# Headend.net
KiCad netlist of a schematic drawn in EAGLE
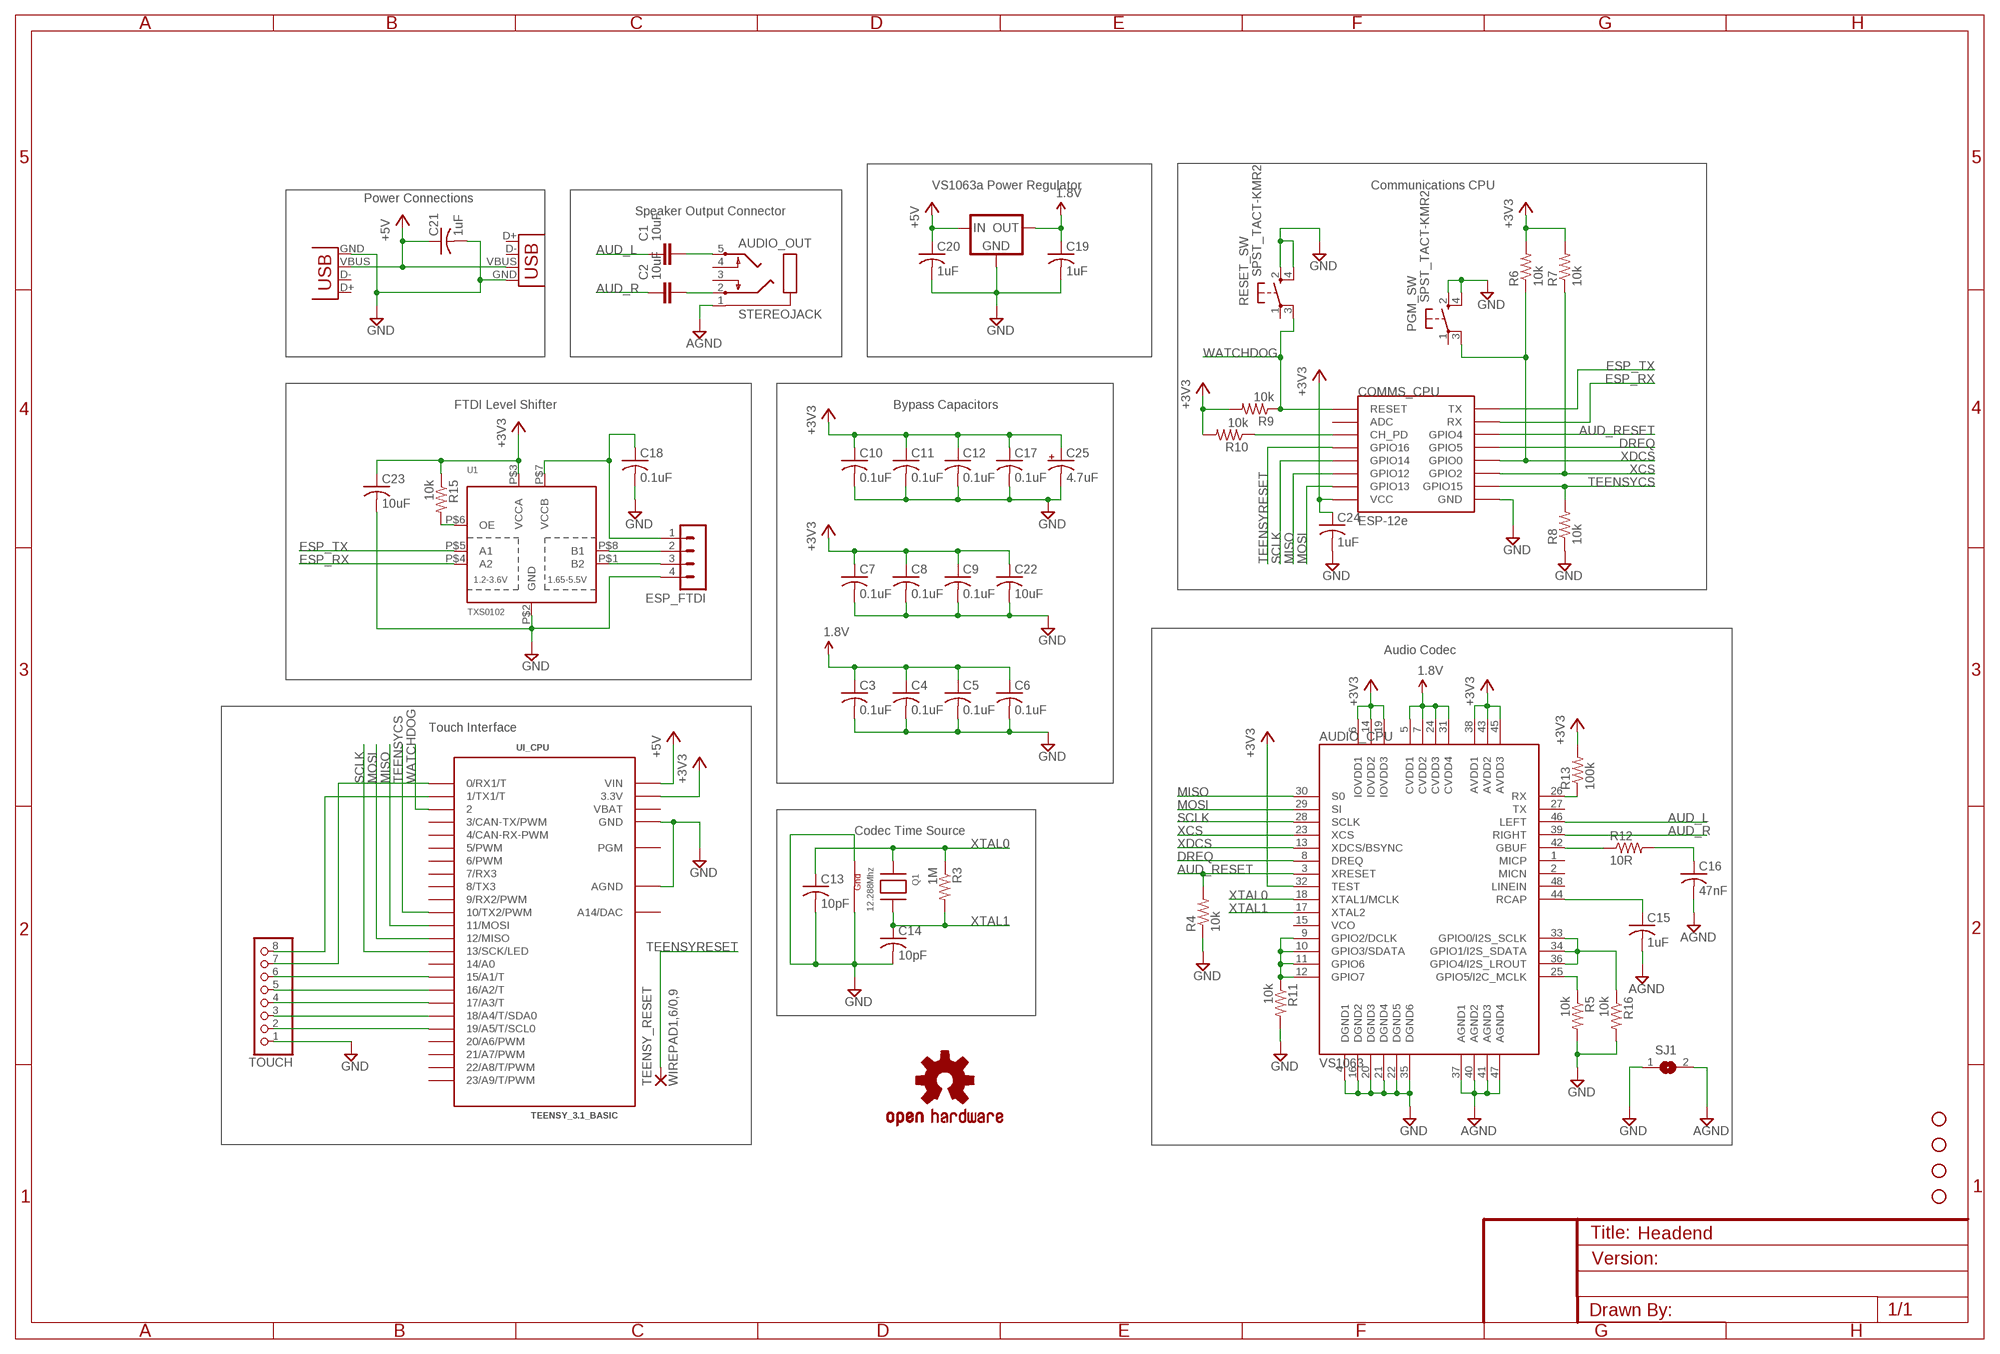
[diagram p0: schematic, sheet 1]

(export (version "E")
  (design (tool "Eeschema 10.0.6"))
  (components
    (comp (ref "AUDIO_CPU")
      (value "VS1063")
      (footprint "eagle-import:LQFP-48")
      (libsource (lib "eagle-import") (part "VS1033"))
    )
    (comp (ref "AUDIO_OUT")
      (value "STEREOJACK")
      (footprint "eagle-import:STX3100")
      (libsource (lib "eagle-import") (part "STEREOJACK"))
    )
    (comp (ref "C1")
      (value "10uF")
      (footprint "eagle-import:C805")
      (libsource (lib "eagle-import") (part "CAPACITOR_NPOL-0805"))
    )
    (comp (ref "C2")
      (value "10uF")
      (footprint "eagle-import:C805")
      (libsource (lib "eagle-import") (part "CAPACITOR_NPOL-0805"))
    )
    (comp (ref "C3")
      (value "0.1uF")
      (footprint "eagle-import:C0402")
      (libsource (lib "eagle-import") (part "C-USC0402"))
    )
    (comp (ref "C4")
      (value "0.1uF")
      (footprint "eagle-import:C0402")
      (libsource (lib "eagle-import") (part "C-USC0402"))
    )
    (comp (ref "C5")
      (value "0.1uF")
      (footprint "eagle-import:C0402")
      (libsource (lib "eagle-import") (part "C-USC0402"))
    )
    (comp (ref "C6")
      (value "0.1uF")
      (footprint "eagle-import:C0402")
      (libsource (lib "eagle-import") (part "C-USC0402"))
    )
    (comp (ref "C7")
      (value "0.1uF")
      (footprint "eagle-import:C0402")
      (libsource (lib "eagle-import") (part "C-USC0402"))
    )
    (comp (ref "C8")
      (value "0.1uF")
      (footprint "eagle-import:C0402")
      (libsource (lib "eagle-import") (part "C-USC0402"))
    )
    (comp (ref "C9")
      (value "0.1uF")
      (footprint "eagle-import:C0402")
      (libsource (lib "eagle-import") (part "C-USC0402"))
    )
    (comp (ref "C10")
      (value "0.1uF")
      (footprint "eagle-import:C0402")
      (libsource (lib "eagle-import") (part "C-USC0402"))
    )
    (comp (ref "C11")
      (value "0.1uF")
      (footprint "eagle-import:C0402")
      (libsource (lib "eagle-import") (part "C-USC0402"))
    )
    (comp (ref "C12")
      (value "0.1uF")
      (footprint "eagle-import:C0402")
      (libsource (lib "eagle-import") (part "C-USC0402"))
    )
    (comp (ref "C13")
      (value "10pF")
      (footprint "eagle-import:C0402")
      (libsource (lib "eagle-import") (part "C-USC0402"))
    )
    (comp (ref "C14")
      (value "10pF")
      (footprint "eagle-import:C0402")
      (libsource (lib "eagle-import") (part "C-USC0402"))
    )
    (comp (ref "C15")
      (value "1uF")
      (footprint "eagle-import:C0402")
      (libsource (lib "eagle-import") (part "C-USC0402"))
    )
    (comp (ref "C16")
      (value "47nF")
      (footprint "eagle-import:C0402")
      (libsource (lib "eagle-import") (part "C-USC0402"))
    )
    (comp (ref "C17")
      (value "0.1uF")
      (footprint "eagle-import:C0402")
      (libsource (lib "eagle-import") (part "C-USC0402"))
    )
    (comp (ref "C18")
      (value "0.1uF")
      (footprint "eagle-import:C0402")
      (libsource (lib "eagle-import") (part "C-USC0402"))
    )
    (comp (ref "C19")
      (value "1uF")
      (footprint "eagle-import:C0603")
      (libsource (lib "eagle-import") (part "C-USC0603"))
    )
    (comp (ref "C20")
      (value "1uF")
      (footprint "eagle-import:C0603")
      (libsource (lib "eagle-import") (part "C-USC0603"))
    )
    (comp (ref "C21")
      (value "1uF")
      (footprint "eagle-import:C0603")
      (libsource (lib "eagle-import") (part "C-USC0603"))
    )
    (comp (ref "C22")
      (value "10uF")
      (footprint "eagle-import:C0402")
      (libsource (lib "eagle-import") (part "C-USC0402"))
    )
    (comp (ref "C23")
      (value "10uF")
      (footprint "eagle-import:C0402")
      (libsource (lib "eagle-import") (part "C-USC0402"))
    )
    (comp (ref "C24")
      (value "1uF")
      (footprint "eagle-import:C0402")
      (libsource (lib "eagle-import") (part "C-USC0402"))
    )
    (comp (ref "C25")
      (value "4.7uF")
      (footprint "eagle-import:PANASONIC_A")
      (libsource (lib "eagle-import") (part "CPOL-USA"))
    )
    (comp (ref "COMMS_CPU")
      (value "ESP-12e")
      (footprint "eagle-import:ESP12-SMD")
      (libsource (lib "eagle-import") (part "ESP12SMD"))
    )
    (comp (ref "ESP_FTDI")
      (value "MA04-1")
      (footprint "eagle-import:MA04-1")
      (libsource (lib "eagle-import") (part "MA04-1"))
    )
    (comp (ref "LOGO1")
      (value "OSHW-LOGOL")
      (footprint "eagle-import:OSHW-LOGO-L")
      (libsource (lib "eagle-import") (part "OSHW-LOGOL"))
    )
    (comp (ref "PGM_SW")
      (value "SPST_TACT-KMR2")
      (footprint "eagle-import:KMR2")
      (libsource (lib "eagle-import") (part "SPST_TACT-KMR2"))
    )
    (comp (ref "POWER_IN")
      (value "USBSMD")
      (footprint "eagle-import:USB-MINIB")
      (libsource (lib "eagle-import") (part "USBSMD"))
    )
    (comp (ref "Q1")
      (value "12.288Mhz")
      (footprint "eagle-import:NX3225")
      (libsource (lib "eagle-import") (part "XTAL-4-3225"))
    )
    (comp (ref "R3")
      (value "1M")
      (footprint "eagle-import:R0402")
      (libsource (lib "eagle-import") (part "R-US_R0402"))
    )
    (comp (ref "R4")
      (value "10k")
      (footprint "eagle-import:R0402")
      (libsource (lib "eagle-import") (part "R-US_R0402"))
    )
    (comp (ref "R5")
      (value "10k")
      (footprint "eagle-import:R0402")
      (libsource (lib "eagle-import") (part "R-US_R0402"))
    )
    (comp (ref "R6")
      (value "10k")
      (footprint "eagle-import:R0402")
      (libsource (lib "eagle-import") (part "R-US_R0402"))
    )
    (comp (ref "R7")
      (value "10k")
      (footprint "eagle-import:R0402")
      (libsource (lib "eagle-import") (part "R-US_R0402"))
    )
    (comp (ref "R8")
      (value "10k")
      (footprint "eagle-import:R0402")
      (libsource (lib "eagle-import") (part "R-US_R0402"))
    )
    (comp (ref "R9")
      (value "10k")
      (footprint "eagle-import:R0603")
      (libsource (lib "eagle-import") (part "R-US_R0603"))
    )
    (comp (ref "R10")
      (value "10k")
      (footprint "eagle-import:R0402")
      (libsource (lib "eagle-import") (part "R-US_R0402"))
    )
    (comp (ref "R11")
      (value "10k")
      (footprint "eagle-import:R0402")
      (libsource (lib "eagle-import") (part "R-US_R0402"))
    )
    (comp (ref "R12")
      (value "10R")
      (footprint "eagle-import:R0402")
      (libsource (lib "eagle-import") (part "R-US_R0402"))
    )
    (comp (ref "R13")
      (value "100k")
      (footprint "eagle-import:R0402")
      (libsource (lib "eagle-import") (part "R-US_R0402"))
    )
    (comp (ref "R15")
      (value "10k")
      (footprint "eagle-import:R0402")
      (libsource (lib "eagle-import") (part "R-US_R0402"))
    )
    (comp (ref "R16")
      (value "10k")
      (footprint "eagle-import:R0402")
      (libsource (lib "eagle-import") (part "R-US_R0402"))
    )
    (comp (ref "RESET_SW")
      (value "SPST_TACT-KMR2")
      (footprint "eagle-import:KMR2")
      (libsource (lib "eagle-import") (part "SPST_TACT-KMR2"))
    )
    (comp (ref "SJ1") (value "SJ") (footprint "eagle-import:SJ") (libsource (lib "eagle-import") (part "SJ")))
    (comp (ref "SPEAKER_PWR2")
      (value "USB-A-S")
      (footprint "eagle-import:USB-A-S")
      (libsource (lib "eagle-import") (part "USB-A-S"))
    )
    (comp (ref "STANDOFF1")
      (value "STAND-OFF")
      (footprint "eagle-import:STAND-OFF")
      (libsource (lib "eagle-import") (part "STAND-OFF"))
    )
    (comp (ref "STANDOFF2")
      (value "STAND-OFF")
      (footprint "eagle-import:STAND-OFF")
      (libsource (lib "eagle-import") (part "STAND-OFF"))
    )
    (comp (ref "STANDOFF3")
      (value "STAND-OFF")
      (footprint "eagle-import:STAND-OFF")
      (libsource (lib "eagle-import") (part "STAND-OFF"))
    )
    (comp (ref "STANDOFF4")
      (value "STAND-OFF")
      (footprint "eagle-import:STAND-OFF")
      (libsource (lib "eagle-import") (part "STAND-OFF"))
    )
    (comp (ref "TEENSY_RESET")
      (value "WIREPAD1,6/0,9")
      (footprint "eagle-import:1,6_0,9")
      (libsource (lib "eagle-import") (part "WIREPAD1,6/0,9"))
    )
    (comp (ref "TOUCH")
      (value "PINHD-1X8BIG")
      (footprint "eagle-import:1X08-BIG")
      (libsource (lib "eagle-import") (part "PINHD-1X8BIG"))
    )
    (comp (ref "U1")
      (value "TXS0102")
      (footprint "eagle-import:VFSOP-8")
      (libsource (lib "eagle-import") (part "TXS0102"))
    )
    (comp (ref "U2")
      (value "AP7313")
      (footprint "eagle-import:SOT23")
      (libsource (lib "eagle-import") (part "AP7313"))
    )
    (comp (ref "UI_CPU")
      (value "TEENSY_3.1_BASIC")
      (footprint "eagle-import:TEENSY_3.1_BASIC")
      (libsource (lib "eagle-import") (part "TEENSY_3.1_BASIC"))
    )
  )
  (nets
    (net (code "1") (name "+3V3") (class "Default")
      (node (ref "AUDIO_CPU") (pin "14") (pinfunction "IOVDD2_14") (pintype "bidirectional"))
      (node (ref "AUDIO_CPU") (pin "19") (pinfunction "IOVDD3_19") (pintype "bidirectional"))
      (node (ref "AUDIO_CPU") (pin "32") (pinfunction "TEST_32") (pintype "bidirectional"))
      (node (ref "AUDIO_CPU") (pin "38") (pinfunction "AVDD1_38") (pintype "bidirectional"))
      (node (ref "AUDIO_CPU") (pin "43") (pinfunction "AVDD2_43") (pintype "bidirectional"))
      (node (ref "AUDIO_CPU") (pin "45") (pinfunction "AVDD3_45") (pintype "bidirectional"))
      (node (ref "AUDIO_CPU") (pin "6") (pinfunction "IOVDD1_6") (pintype "bidirectional"))
      (node (ref "C10") (pin "1") (pinfunction "1_1") (pintype "passive"))
      (node (ref "C11") (pin "1") (pinfunction "1_1") (pintype "passive"))
      (node (ref "C12") (pin "1") (pinfunction "1_1") (pintype "passive"))
      (node (ref "C17") (pin "1") (pinfunction "1_1") (pintype "passive"))
      (node (ref "C22") (pin "1") (pinfunction "1_1") (pintype "passive"))
      (node (ref "C23") (pin "1") (pinfunction "1_1") (pintype "passive"))
      (node (ref "C24") (pin "1") (pinfunction "1_1") (pintype "passive"))
      (node (ref "C25") (pin "+") (pinfunction "+_+") (pintype "passive"))
      (node (ref "C7") (pin "1") (pinfunction "1_1") (pintype "passive"))
      (node (ref "C8") (pin "1") (pinfunction "1_1") (pintype "passive"))
      (node (ref "C9") (pin "1") (pinfunction "1_1") (pintype "passive"))
      (node (ref "COMMS_CPU") (pin "VCC") (pinfunction "VCC_VCC") (pintype "bidirectional"))
      (node (ref "R10") (pin "2") (pinfunction "2_2") (pintype "passive"))
      (node (ref "R13") (pin "2") (pinfunction "2_2") (pintype "passive"))
      (node (ref "R15") (pin "1") (pinfunction "1_1") (pintype "passive"))
      (node (ref "R6") (pin "2") (pinfunction "2_2") (pintype "passive"))
      (node (ref "R7") (pin "2") (pinfunction "2_2") (pintype "passive"))
      (node (ref "R9") (pin "2") (pinfunction "2_2") (pintype "passive"))
      (node (ref "U1") (pin "P$3") (pinfunction "VCCA_P$3") (pintype "bidirectional"))
      (node (ref "UI_CPU") (pin "3.3V") (pinfunction "3.3V_3.3V") (pintype "power_in"))
      (node (ref "UI_CPU") (pin "3.3V1") (pinfunction "3.3V_3.3V1") (pintype "power_in"))
    )
    (net (code "2") (name "+5V") (class "Default")
      (node (ref "C20") (pin "1") (pinfunction "1_1") (pintype "passive"))
      (node (ref "C21") (pin "1") (pinfunction "1_1") (pintype "passive"))
      (node (ref "POWER_IN") (pin "VBUS") (pinfunction "VBUS_VBUS") (pintype "bidirectional"))
      (node (ref "SPEAKER_PWR2") (pin "VBUS") (pinfunction "VBUS_VBUS") (pintype "bidirectional"))
      (node (ref "U2") (pin "1") (pinfunction "IN_1") (pintype "input"))
      (node (ref "UI_CPU") (pin "VIN") (pinfunction "VIN_VIN") (pintype "power_in"))
    )
    (net (code "3") (name "/AUD_L") (class "Default")
      (node (ref "AUDIO_CPU") (pin "46") (pinfunction "LEFT_46") (pintype "bidirectional"))
      (node (ref "C1") (pin "1") (pinfunction "1_1") (pintype "passive"))
    )
    (net (code "4") (name "/AUD_R") (class "Default")
      (node (ref "AUDIO_CPU") (pin "39") (pinfunction "RIGHT_39") (pintype "bidirectional"))
      (node (ref "C2") (pin "1") (pinfunction "1_1") (pintype "passive"))
    )
    (net (code "5") (name "/AUD_RESET") (class "Default")
      (node (ref "AUDIO_CPU") (pin "3") (pinfunction "XRESET_3") (pintype "bidirectional"))
      (node (ref "COMMS_CPU") (pin "GPIO4") (pinfunction "GPIO4_GPIO4") (pintype "bidirectional"))
      (node (ref "R4") (pin "2") (pinfunction "2_2") (pintype "passive"))
    )
    (net (code "6") (name "/DREQ") (class "Default")
      (node (ref "AUDIO_CPU") (pin "8") (pinfunction "DREQ_8") (pintype "bidirectional"))
      (node (ref "COMMS_CPU") (pin "GPIO5") (pinfunction "GPIO5_GPIO5") (pintype "bidirectional"))
    )
    (net (code "7") (name "/ESP_RX") (class "Default")
      (node (ref "COMMS_CPU") (pin "RXD0") (pinfunction "RX_RXD0") (pintype "bidirectional"))
      (node (ref "U1") (pin "P$4") (pinfunction "A2_P$4") (pintype "bidirectional"))
    )
    (net (code "8") (name "/ESP_TX") (class "Default")
      (node (ref "COMMS_CPU") (pin "TXD0") (pinfunction "TX_TXD0") (pintype "bidirectional"))
      (node (ref "U1") (pin "P$5") (pinfunction "A1_P$5") (pintype "bidirectional"))
    )
    (net (code "9") (name "/MISO") (class "Default")
      (node (ref "AUDIO_CPU") (pin "30") (pinfunction "S0_30") (pintype "bidirectional"))
      (node (ref "COMMS_CPU") (pin "GPIO12") (pinfunction "GPIO12_GPIO12") (pintype "bidirectional"))
      (node (ref "UI_CPU") (pin "11") (pinfunction "11/MOSI_11") (pintype "bidirectional"))
    )
    (net (code "10") (name "/MOSI") (class "Default")
      (node (ref "AUDIO_CPU") (pin "29") (pinfunction "SI_29") (pintype "bidirectional"))
      (node (ref "COMMS_CPU") (pin "GPIO13") (pinfunction "GPIO13_GPIO13") (pintype "bidirectional"))
      (node (ref "UI_CPU") (pin "12") (pinfunction "12/MISO_12") (pintype "bidirectional"))
    )
    (net (code "11") (name "/SCLK") (class "Default")
      (node (ref "AUDIO_CPU") (pin "28") (pinfunction "SCLK_28") (pintype "bidirectional"))
      (node (ref "COMMS_CPU") (pin "GPIO14") (pinfunction "GPIO14_GPIO14") (pintype "bidirectional"))
      (node (ref "UI_CPU") (pin "13") (pinfunction "13/SCK/LED_13") (pintype "bidirectional"))
    )
    (net (code "12") (name "/TEENSYCS") (class "Default")
      (node (ref "COMMS_CPU") (pin "GPIO15") (pinfunction "GPIO15_GPIO15") (pintype "bidirectional"))
      (node (ref "R8") (pin "2") (pinfunction "2_2") (pintype "passive"))
      (node (ref "UI_CPU") (pin "10") (pinfunction "10/TX2/PWM_10") (pintype "bidirectional"))
    )
    (net (code "13") (name "/TEENSYRESET") (class "Default")
      (node (ref "COMMS_CPU") (pin "GPIO16") (pinfunction "GPIO16_GPIO16") (pintype "bidirectional"))
      (node (ref "TEENSY_RESET") (pin "1") (pinfunction "P_1") (pintype "passive"))
    )
    (net (code "14") (name "/VBAT") (class "Default")
      (node (ref "UI_CPU") (pin "VBAT") (pinfunction "VBAT_VBAT") (pintype "power_in"))
    )
    (net (code "15") (name "/WATCHDOG") (class "Default")
      (node (ref "COMMS_CPU") (pin "RESET") (pinfunction "RESET_RESET") (pintype "bidirectional"))
      (node (ref "R9") (pin "1") (pinfunction "1_1") (pintype "passive"))
      (node (ref "RESET_SW") (pin "3") (pinfunction "P1_3") (pintype "passive"))
      (node (ref "UI_CPU") (pin "2") (pinfunction "2_2") (pintype "bidirectional"))
    )
    (net (code "16") (name "/XCS") (class "Default")
      (node (ref "AUDIO_CPU") (pin "23") (pinfunction "XCS_23") (pintype "bidirectional"))
      (node (ref "COMMS_CPU") (pin "GPIO2") (pinfunction "GPIO2_GPIO2") (pintype "bidirectional"))
      (node (ref "R7") (pin "1") (pinfunction "1_1") (pintype "passive"))
    )
    (net (code "17") (name "/XDCS") (class "Default")
      (node (ref "AUDIO_CPU") (pin "13") (pinfunction "XDCS/BSYNC_13") (pintype "bidirectional"))
      (node (ref "COMMS_CPU") (pin "GPIO0") (pinfunction "GPIO0_GPIO0") (pintype "bidirectional"))
      (node (ref "PGM_SW") (pin "3") (pinfunction "P1_3") (pintype "passive"))
      (node (ref "R6") (pin "1") (pinfunction "1_1") (pintype "passive"))
    )
    (net (code "18") (name "/XTAL0") (class "Default")
      (node (ref "AUDIO_CPU") (pin "18") (pinfunction "XTAL1/MCLK_18") (pintype "bidirectional"))
      (node (ref "C13") (pin "1") (pinfunction "1_1") (pintype "passive"))
      (node (ref "Q1") (pin "1") (pinfunction "X1_1") (pintype "bidirectional"))
      (node (ref "R3") (pin "1") (pinfunction "1_1") (pintype "passive"))
    )
    (net (code "19") (name "/XTAL1") (class "Default")
      (node (ref "AUDIO_CPU") (pin "17") (pinfunction "XTAL2_17") (pintype "bidirectional"))
      (node (ref "C14") (pin "1") (pinfunction "1_1") (pintype "passive"))
      (node (ref "Q1") (pin "3") (pinfunction "X2_3") (pintype "bidirectional"))
      (node (ref "R3") (pin "2") (pinfunction "2_2") (pintype "passive"))
    )
    (net (code "20") (name "1.8V") (class "Default")
      (node (ref "AUDIO_CPU") (pin "24") (pinfunction "CVDD3_24") (pintype "bidirectional"))
      (node (ref "AUDIO_CPU") (pin "31") (pinfunction "CVDD4_31") (pintype "bidirectional"))
      (node (ref "AUDIO_CPU") (pin "5") (pinfunction "CVDD1_5") (pintype "bidirectional"))
      (node (ref "AUDIO_CPU") (pin "7") (pinfunction "CVDD2_7") (pintype "bidirectional"))
      (node (ref "C19") (pin "1") (pinfunction "1_1") (pintype "passive"))
      (node (ref "C3") (pin "1") (pinfunction "1_1") (pintype "passive"))
      (node (ref "C4") (pin "1") (pinfunction "1_1") (pintype "passive"))
      (node (ref "C5") (pin "1") (pinfunction "1_1") (pintype "passive"))
      (node (ref "C6") (pin "1") (pinfunction "1_1") (pintype "passive"))
      (node (ref "U2") (pin "2") (pinfunction "OUT_2") (pintype "output"))
    )
    (net (code "21") (name "AGND") (class "Default")
      (node (ref "AUDIO_CPU") (pin "37") (pinfunction "AGND1_37") (pintype "bidirectional"))
      (node (ref "AUDIO_CPU") (pin "40") (pinfunction "AGND2_40") (pintype "bidirectional"))
      (node (ref "AUDIO_CPU") (pin "41") (pinfunction "AGND3_41") (pintype "bidirectional"))
      (node (ref "AUDIO_CPU") (pin "47") (pinfunction "AGND4_47") (pintype "bidirectional"))
      (node (ref "AUDIO_OUT") (pin "1") (pinfunction "1_1") (pintype "passive"))
      (node (ref "C15") (pin "2") (pinfunction "2_2") (pintype "passive"))
      (node (ref "C16") (pin "2") (pinfunction "2_2") (pintype "passive"))
      (node (ref "SJ1") (pin "2") (pinfunction "2_2") (pintype "passive"))
    )
    (net (code "22") (name "GND") (class "Default")
      (node (ref "AUDIO_CPU") (pin "16") (pinfunction "DGND2_16") (pintype "bidirectional"))
      (node (ref "AUDIO_CPU") (pin "20") (pinfunction "DGND3_20") (pintype "bidirectional"))
      (node (ref "AUDIO_CPU") (pin "21") (pinfunction "DGND4_21") (pintype "bidirectional"))
      (node (ref "AUDIO_CPU") (pin "22") (pinfunction "DGND5_22") (pintype "bidirectional"))
      (node (ref "AUDIO_CPU") (pin "35") (pinfunction "DGND6_35") (pintype "bidirectional"))
      (node (ref "AUDIO_CPU") (pin "4") (pinfunction "DGND1_4") (pintype "bidirectional"))
      (node (ref "C10") (pin "2") (pinfunction "2_2") (pintype "passive"))
      (node (ref "C11") (pin "2") (pinfunction "2_2") (pintype "passive"))
      (node (ref "C12") (pin "2") (pinfunction "2_2") (pintype "passive"))
      (node (ref "C13") (pin "2") (pinfunction "2_2") (pintype "passive"))
      (node (ref "C14") (pin "2") (pinfunction "2_2") (pintype "passive"))
      (node (ref "C17") (pin "2") (pinfunction "2_2") (pintype "passive"))
      (node (ref "C18") (pin "2") (pinfunction "2_2") (pintype "passive"))
      (node (ref "C19") (pin "2") (pinfunction "2_2") (pintype "passive"))
      (node (ref "C20") (pin "2") (pinfunction "2_2") (pintype "passive"))
      (node (ref "C21") (pin "2") (pinfunction "2_2") (pintype "passive"))
      (node (ref "C22") (pin "2") (pinfunction "2_2") (pintype "passive"))
      (node (ref "C23") (pin "2") (pinfunction "2_2") (pintype "passive"))
      (node (ref "C24") (pin "2") (pinfunction "2_2") (pintype "passive"))
      (node (ref "C25") (pin "-") (pinfunction "-_-") (pintype "passive"))
      (node (ref "C3") (pin "2") (pinfunction "2_2") (pintype "passive"))
      (node (ref "C4") (pin "2") (pinfunction "2_2") (pintype "passive"))
      (node (ref "C5") (pin "2") (pinfunction "2_2") (pintype "passive"))
      (node (ref "C6") (pin "2") (pinfunction "2_2") (pintype "passive"))
      (node (ref "C7") (pin "2") (pinfunction "2_2") (pintype "passive"))
      (node (ref "C8") (pin "2") (pinfunction "2_2") (pintype "passive"))
      (node (ref "C9") (pin "2") (pinfunction "2_2") (pintype "passive"))
      (node (ref "COMMS_CPU") (pin "GND") (pinfunction "GND_GND") (pintype "bidirectional"))
      (node (ref "ESP_FTDI") (pin "4") (pinfunction "4_4") (pintype "passive"))
      (node (ref "PGM_SW") (pin "2") (pinfunction "S_2") (pintype "passive"))
      (node (ref "PGM_SW") (pin "4") (pinfunction "S1_4") (pintype "passive"))
      (node (ref "POWER_IN") (pin "GND") (pinfunction "GND_GND") (pintype "bidirectional"))
      (node (ref "Q1") (pin "2") (pinfunction "G2_2") (pintype "power_in"))
      (node (ref "Q1") (pin "4") (pinfunction "G1_4") (pintype "power_in"))
      (node (ref "R11") (pin "2") (pinfunction "2_2") (pintype "passive"))
      (node (ref "R16") (pin "2") (pinfunction "2_2") (pintype "passive"))
      (node (ref "R4") (pin "1") (pinfunction "1_1") (pintype "passive"))
      (node (ref "R5") (pin "2") (pinfunction "2_2") (pintype "passive"))
      (node (ref "R8") (pin "1") (pinfunction "1_1") (pintype "passive"))
      (node (ref "RESET_SW") (pin "2") (pinfunction "S_2") (pintype "passive"))
      (node (ref "RESET_SW") (pin "4") (pinfunction "S1_4") (pintype "passive"))
      (node (ref "SJ1") (pin "1") (pinfunction "1_1") (pintype "passive"))
      (node (ref "SPEAKER_PWR2") (pin "GND") (pinfunction "GND_GND") (pintype "bidirectional"))
      (node (ref "TOUCH") (pin "1") (pinfunction "1_1") (pintype "passive"))
      (node (ref "U1") (pin "P$2") (pinfunction "GND_P$2") (pintype "bidirectional"))
      (node (ref "U2") (pin "3") (pinfunction "GND_3") (pintype "input"))
      (node (ref "UI_CPU") (pin "AGND") (pinfunction "AGND_AGND") (pintype "power_in"))
      (node (ref "UI_CPU") (pin "GND") (pinfunction "GND_GND") (pintype "power_in"))
      (node (ref "UI_CPU") (pin "GND1") (pinfunction "GND_GND1") (pintype "power_in"))
    )
    (net (code "23") (name "Net-(AUDIO_CPU-GBUF)") (class "Default")
      (node (ref "AUDIO_CPU") (pin "42") (pinfunction "GBUF_42") (pintype "bidirectional"))
      (node (ref "R12") (pin "1") (pinfunction "1_1") (pintype "passive"))
    )
    (net (code "24") (name "Net-(AUDIO_CPU-GPIO0{slash}I2S_SCLK)") (class "Default")
      (node (ref "AUDIO_CPU") (pin "33") (pinfunction "GPIO0/I2S_SCLK_33") (pintype "bidirectional"))
      (node (ref "AUDIO_CPU") (pin "34") (pinfunction "GPIO1/I2S_SDATA_34") (pintype "bidirectional"))
      (node (ref "AUDIO_CPU") (pin "36") (pinfunction "GPIO4/I2S_LROUT_36") (pintype "bidirectional"))
      (node (ref "R16") (pin "1") (pinfunction "1_1") (pintype "passive"))
    )
    (net (code "25") (name "Net-(AUDIO_CPU-GPIO2{slash}DCLK)") (class "Default")
      (node (ref "AUDIO_CPU") (pin "10") (pinfunction "GPIO3/SDATA_10") (pintype "bidirectional"))
      (node (ref "AUDIO_CPU") (pin "11") (pinfunction "GPIO6_11") (pintype "bidirectional"))
      (node (ref "AUDIO_CPU") (pin "12") (pinfunction "GPIO7_12") (pintype "bidirectional"))
      (node (ref "AUDIO_CPU") (pin "9") (pinfunction "GPIO2/DCLK_9") (pintype "bidirectional"))
      (node (ref "R11") (pin "1") (pinfunction "1_1") (pintype "passive"))
    )
    (net (code "26") (name "Net-(AUDIO_CPU-GPIO5{slash}I2C_MCLK)") (class "Default")
      (node (ref "AUDIO_CPU") (pin "25") (pinfunction "GPIO5/I2C_MCLK_25") (pintype "bidirectional"))
      (node (ref "R5") (pin "1") (pinfunction "1_1") (pintype "passive"))
    )
    (net (code "27") (name "Net-(AUDIO_CPU-RCAP)") (class "Default")
      (node (ref "AUDIO_CPU") (pin "44") (pinfunction "RCAP_44") (pintype "bidirectional"))
      (node (ref "C15") (pin "1") (pinfunction "1_1") (pintype "passive"))
    )
    (net (code "28") (name "Net-(AUDIO_CPU-RX)") (class "Default")
      (node (ref "AUDIO_CPU") (pin "26") (pinfunction "RX_26") (pintype "bidirectional"))
      (node (ref "R13") (pin "1") (pinfunction "1_1") (pintype "passive"))
    )
    (net (code "29") (name "Net-(AUDIO_OUT-Pad2)") (class "Default")
      (node (ref "AUDIO_OUT") (pin "2") (pinfunction "2_2") (pintype "passive"))
      (node (ref "C2") (pin "2") (pinfunction "2_2") (pintype "passive"))
    )
    (net (code "30") (name "Net-(AUDIO_OUT-Pad5)") (class "Default")
      (node (ref "AUDIO_OUT") (pin "5") (pinfunction "5_5") (pintype "passive"))
      (node (ref "C1") (pin "2") (pinfunction "2_2") (pintype "passive"))
    )
    (net (code "31") (name "Net-(C16-Pad1)") (class "Default")
      (node (ref "C16") (pin "1") (pinfunction "1_1") (pintype "passive"))
      (node (ref "R12") (pin "2") (pinfunction "2_2") (pintype "passive"))
    )
    (net (code "32") (name "Net-(COMMS_CPU-PadCH_PD)") (class "Default")
      (node (ref "COMMS_CPU") (pin "CH_PD") (pinfunction "CH_PD_CH_PD") (pintype "bidirectional"))
      (node (ref "R10") (pin "1") (pinfunction "1_1") (pintype "passive"))
    )
    (net (code "33") (name "Net-(U1-B1)") (class "Default")
      (node (ref "ESP_FTDI") (pin "2") (pinfunction "2_2") (pintype "passive"))
      (node (ref "U1") (pin "P$8") (pinfunction "B1_P$8") (pintype "bidirectional"))
    )
    (net (code "34") (name "Net-(U1-B2)") (class "Default")
      (node (ref "ESP_FTDI") (pin "3") (pinfunction "3_3") (pintype "passive"))
      (node (ref "U1") (pin "P$1") (pinfunction "B2_P$1") (pintype "bidirectional"))
    )
    (net (code "35") (name "Net-(U1-OE)") (class "Default")
      (node (ref "R15") (pin "2") (pinfunction "2_2") (pintype "passive"))
      (node (ref "U1") (pin "P$6") (pinfunction "OE_P$6") (pintype "bidirectional"))
    )
    (net (code "36") (name "Net-(U1-VCCB)") (class "Default")
      (node (ref "C18") (pin "1") (pinfunction "1_1") (pintype "passive"))
      (node (ref "ESP_FTDI") (pin "1") (pinfunction "1_1") (pintype "passive"))
      (node (ref "U1") (pin "P$7") (pinfunction "VCCB_P$7") (pintype "bidirectional"))
    )
    (net (code "37") (name "Net-(UI_CPU-0{slash}RX1{slash}T)") (class "Default")
      (node (ref "TOUCH") (pin "7") (pinfunction "7_7") (pintype "passive"))
      (node (ref "UI_CPU") (pin "0") (pinfunction "0/RX1/T_0") (pintype "bidirectional"))
    )
    (net (code "38") (name "Net-(UI_CPU-1{slash}TX1{slash}T)") (class "Default")
      (node (ref "TOUCH") (pin "8") (pinfunction "8_8") (pintype "passive"))
      (node (ref "UI_CPU") (pin "1") (pinfunction "1/TX1/T_1") (pintype "bidirectional"))
    )
    (net (code "39") (name "Net-(UI_CPU-15{slash}A1{slash}T)") (class "Default")
      (node (ref "TOUCH") (pin "6") (pinfunction "6_6") (pintype "passive"))
      (node (ref "UI_CPU") (pin "15/A1") (pinfunction "15/A1/T_15/A1") (pintype "bidirectional"))
    )
    (net (code "40") (name "Net-(UI_CPU-16{slash}A2{slash}T)") (class "Default")
      (node (ref "TOUCH") (pin "5") (pinfunction "5_5") (pintype "passive"))
      (node (ref "UI_CPU") (pin "16/A2") (pinfunction "16/A2/T_16/A2") (pintype "bidirectional"))
    )
    (net (code "41") (name "Net-(UI_CPU-17{slash}A3{slash}T)") (class "Default")
      (node (ref "TOUCH") (pin "4") (pinfunction "4_4") (pintype "passive"))
      (node (ref "UI_CPU") (pin "17/A3") (pinfunction "17/A3/T_17/A3") (pintype "bidirectional"))
    )
    (net (code "42") (name "Net-(UI_CPU-18{slash}A4{slash}T{slash}SDA0)") (class "Default")
      (node (ref "TOUCH") (pin "3") (pinfunction "3_3") (pintype "passive"))
      (node (ref "UI_CPU") (pin "18/A4") (pinfunction "18/A4/T/SDA0_18/A4") (pintype "bidirectional"))
    )
    (net (code "43") (name "Net-(UI_CPU-19{slash}A5{slash}T{slash}SCL0)") (class "Default")
      (node (ref "TOUCH") (pin "2") (pinfunction "2_2") (pintype "passive"))
      (node (ref "UI_CPU") (pin "19/A5") (pinfunction "19/A5/T/SCL0_19/A5") (pintype "bidirectional"))
    )
    (net (code "44") (name "unconnected-(AUDIO_CPU-LINEIN-Pad48)") (class "Default")
      (node (ref "AUDIO_CPU") (pin "48") (pinfunction "LINEIN_48") (pintype "bidirectional"))
    )
    (net (code "45") (name "unconnected-(AUDIO_CPU-MICN-Pad2)") (class "Default")
      (node (ref "AUDIO_CPU") (pin "2") (pinfunction "MICN_2") (pintype "bidirectional"))
    )
    (net (code "46") (name "unconnected-(AUDIO_CPU-MICP-Pad1)") (class "Default")
      (node (ref "AUDIO_CPU") (pin "1") (pinfunction "MICP_1") (pintype "bidirectional"))
    )
    (net (code "47") (name "unconnected-(AUDIO_CPU-TX-Pad27)") (class "Default")
      (node (ref "AUDIO_CPU") (pin "27") (pinfunction "TX_27") (pintype "bidirectional"))
    )
    (net (code "48") (name "unconnected-(AUDIO_CPU-VCO-Pad15)") (class "Default")
      (node (ref "AUDIO_CPU") (pin "15") (pinfunction "VCO_15") (pintype "bidirectional"))
    )
    (net (code "49") (name "unconnected-(AUDIO_OUT-Pad3)") (class "Default")
      (node (ref "AUDIO_OUT") (pin "3") (pinfunction "3_3") (pintype "passive"))
    )
    (net (code "50") (name "unconnected-(AUDIO_OUT-Pad4)") (class "Default")
      (node (ref "AUDIO_OUT") (pin "4") (pinfunction "4_4") (pintype "passive"))
    )
    (net (code "51") (name "unconnected-(COMMS_CPU-PadADC)") (class "Default")
      (node (ref "COMMS_CPU") (pin "ADC") (pinfunction "ADC_ADC") (pintype "bidirectional"))
    )
    (net (code "52") (name "unconnected-(PGM_SW-P-Pad1)") (class "Default")
      (node (ref "PGM_SW") (pin "1") (pinfunction "P_1") (pintype "passive"))
    )
    (net (code "53") (name "unconnected-(POWER_IN-PadD+)") (class "Default")
      (node (ref "POWER_IN") (pin "D+") (pinfunction "D+_D+") (pintype "bidirectional"))
    )
    (net (code "54") (name "unconnected-(POWER_IN-PadD-)") (class "Default")
      (node (ref "POWER_IN") (pin "D-") (pinfunction "D-_D-") (pintype "bidirectional"))
    )
    (net (code "55") (name "unconnected-(RESET_SW-P-Pad1)") (class "Default")
      (node (ref "RESET_SW") (pin "1") (pinfunction "P_1") (pintype "passive"))
    )
    (net (code "56") (name "unconnected-(SPEAKER_PWR2-PadD+)") (class "Default")
      (node (ref "SPEAKER_PWR2") (pin "D+") (pinfunction "D+_D+") (pintype "bidirectional"))
    )
    (net (code "57") (name "unconnected-(SPEAKER_PWR2-PadD-)") (class "Default")
      (node (ref "SPEAKER_PWR2") (pin "D-") (pinfunction "D-_D-") (pintype "bidirectional"))
    )
    (net (code "58") (name "unconnected-(UI_CPU-3{slash}CAN-TX{slash}PWM-Pad3)") (class "Default")
      (node (ref "UI_CPU") (pin "3") (pinfunction "3/CAN-TX/PWM_3") (pintype "bidirectional"))
    )
    (net (code "59") (name "unconnected-(UI_CPU-4{slash}CAN-RX-PWM-Pad4)") (class "Default")
      (node (ref "UI_CPU") (pin "4") (pinfunction "4/CAN-RX-PWM_4") (pintype "bidirectional"))
    )
    (net (code "60") (name "unconnected-(UI_CPU-5{slash}PWM-Pad5)") (class "Default")
      (node (ref "UI_CPU") (pin "5") (pinfunction "5/PWM_5") (pintype "bidirectional"))
    )
    (net (code "61") (name "unconnected-(UI_CPU-6{slash}PWM-Pad6)") (class "Default")
      (node (ref "UI_CPU") (pin "6") (pinfunction "6/PWM_6") (pintype "bidirectional"))
    )
    (net (code "62") (name "unconnected-(UI_CPU-7{slash}RX3-Pad7)") (class "Default")
      (node (ref "UI_CPU") (pin "7") (pinfunction "7/RX3_7") (pintype "bidirectional"))
    )
    (net (code "63") (name "unconnected-(UI_CPU-8{slash}TX3-Pad8)") (class "Default")
      (node (ref "UI_CPU") (pin "8") (pinfunction "8/TX3_8") (pintype "bidirectional"))
    )
    (net (code "64") (name "unconnected-(UI_CPU-9{slash}RX2{slash}PWM-Pad9)") (class "Default")
      (node (ref "UI_CPU") (pin "9") (pinfunction "9/RX2/PWM_9") (pintype "bidirectional"))
    )
    (net (code "65") (name "unconnected-(UI_CPU-20{slash}A6{slash}PWM-Pad20{slash}A6)") (class "Default")
      (node (ref "UI_CPU") (pin "20/A6") (pinfunction "20/A6/PWM_20/A6") (pintype "bidirectional"))
    )
    (net (code "66") (name "unconnected-(UI_CPU-21{slash}A7{slash}PWM-Pad21{slash}A7)") (class "Default")
      (node (ref "UI_CPU") (pin "21/A7") (pinfunction "21/A7/PWM_21/A7") (pintype "bidirectional"))
    )
    (net (code "67") (name "unconnected-(UI_CPU-22{slash}A8{slash}T{slash}PWM-Pad22{slash}A8)") (class "Default")
      (node (ref "UI_CPU") (pin "22/A8") (pinfunction "22/A8/T/PWM_22/A8") (pintype "bidirectional"))
    )
    (net (code "68") (name "unconnected-(UI_CPU-23{slash}A9{slash}T{slash}PWM-Pad23{slash}A9)") (class "Default")
      (node (ref "UI_CPU") (pin "23/A9") (pinfunction "23/A9/T/PWM_23/A9") (pintype "bidirectional"))
    )
    (net (code "69") (name "unconnected-(UI_CPU-A14{slash}DAC-PadA14)") (class "Default")
      (node (ref "UI_CPU") (pin "A14") (pinfunction "A14/DAC_A14") (pintype "bidirectional"))
    )
    (net (code "70") (name "unconnected-(UI_CPU-Pad14{slash}A0)") (class "Default")
      (node (ref "UI_CPU") (pin "14/A0") (pinfunction "14/A0_14/A0") (pintype "bidirectional"))
    )
    (net (code "71") (name "unconnected-(UI_CPU-PadPGM)") (class "Default")
      (node (ref "UI_CPU") (pin "PGM") (pinfunction "PGM_PGM") (pintype "bidirectional"))
    )
  )
)
